# relay_board.net
KiCad netlist of a schematic drawn in EAGLE
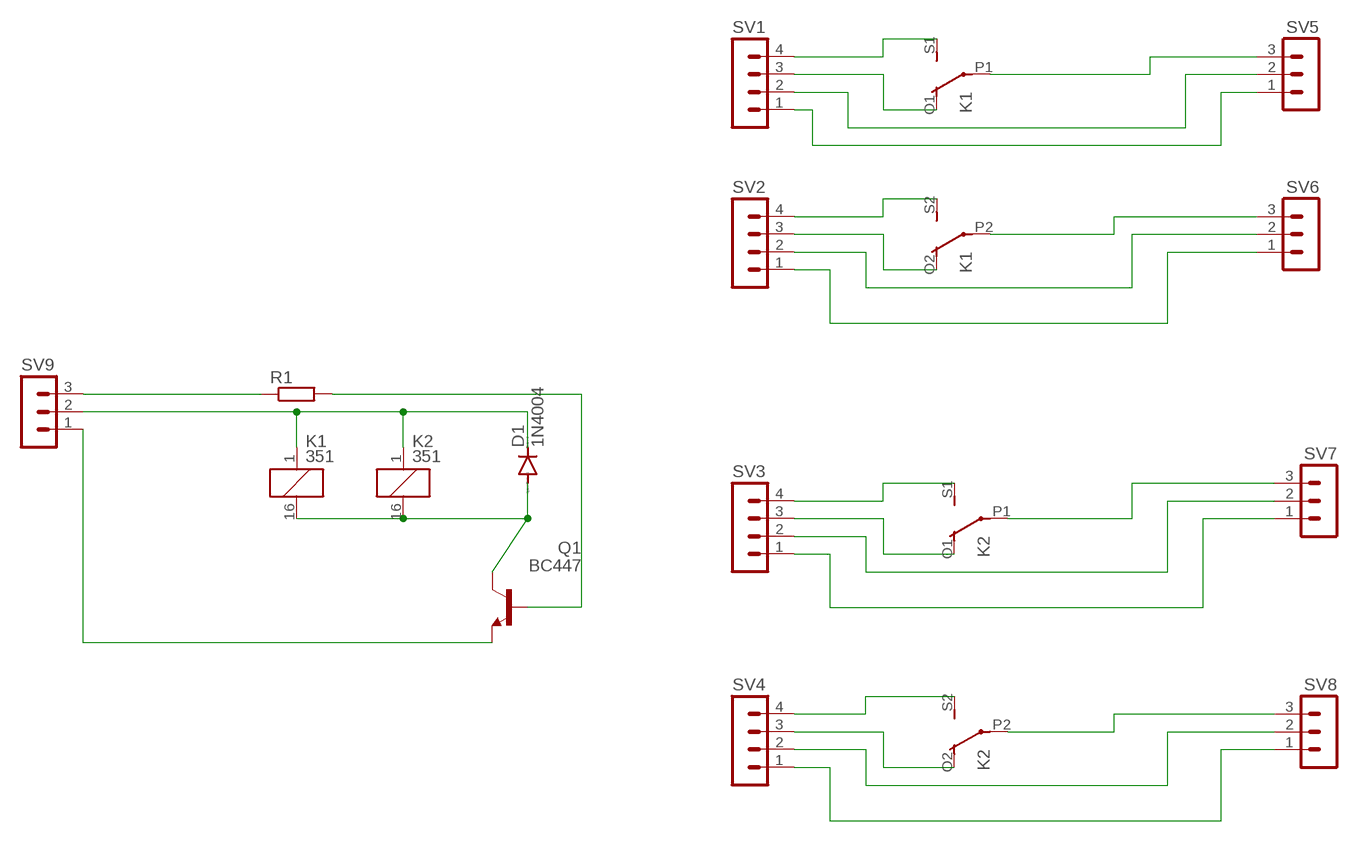
[diagram p0: schematic, sheet 1]

(export (version "E")
  (design (tool "Eeschema 10.0.6"))
  (components
    (comp (ref "D1")
      (value "1N4004")
      (footprint "eagle-import:DO41-10")
      (libsource (lib "eagle-import") (part "1N4004"))
    )
    (comp (ref "K1")
      (value "351")
      (footprint "eagle-import:351")
      (libsource (lib "eagle-import") (part "351"))
    )
    (comp (ref "K2")
      (value "351")
      (footprint "eagle-import:351")
      (libsource (lib "eagle-import") (part "351"))
    )
    (comp (ref "Q1")
      (value "BC447")
      (footprint "eagle-import:TO92-EBC")
      (libsource (lib "eagle-import") (part "BC447"))
    )
    (comp (ref "R1")
      (value "R-EU_0207/15")
      (footprint "eagle-import:0207_15")
      (libsource (lib "eagle-import") (part "R-EU_0207/15"))
    )
    (comp (ref "SV1")
      (value "MA04-1")
      (footprint "eagle-import:MA04-1")
      (libsource (lib "eagle-import") (part "MA04-1"))
    )
    (comp (ref "SV2")
      (value "MA04-1")
      (footprint "eagle-import:MA04-1")
      (libsource (lib "eagle-import") (part "MA04-1"))
    )
    (comp (ref "SV3")
      (value "MA04-1")
      (footprint "eagle-import:MA04-1")
      (libsource (lib "eagle-import") (part "MA04-1"))
    )
    (comp (ref "SV4")
      (value "MA04-1")
      (footprint "eagle-import:MA04-1")
      (libsource (lib "eagle-import") (part "MA04-1"))
    )
    (comp (ref "SV5")
      (value "MA03-1")
      (footprint "eagle-import:MA03-1")
      (libsource (lib "eagle-import") (part "MA03-1"))
    )
    (comp (ref "SV6")
      (value "MA03-1")
      (footprint "eagle-import:MA03-1")
      (libsource (lib "eagle-import") (part "MA03-1"))
    )
    (comp (ref "SV7")
      (value "MA03-1")
      (footprint "eagle-import:MA03-1")
      (libsource (lib "eagle-import") (part "MA03-1"))
    )
    (comp (ref "SV8")
      (value "MA03-1")
      (footprint "eagle-import:MA03-1")
      (libsource (lib "eagle-import") (part "MA03-1"))
    )
    (comp (ref "SV9")
      (value "MA03-1")
      (footprint "eagle-import:MA03-1")
      (libsource (lib "eagle-import") (part "MA03-1"))
    )
  )
  (nets
    (net (code "1") (name "Net-(D1-PadC)") (class "Default")
      (node (ref "D1") (pin "C") (pinfunction "C_C") (pintype "passive"))
      (node (ref "K1") (pin "1") (pinfunction "1_1") (pintype "passive"))
      (node (ref "K2") (pin "1") (pinfunction "1_1") (pintype "passive"))
      (node (ref "SV9") (pin "2") (pinfunction "2_2") (pintype "passive"))
    )
    (net (code "2") (name "Net-(K1A-2)") (class "Default")
      (node (ref "D1") (pin "A") (pinfunction "A_A") (pintype "passive"))
      (node (ref "K1") (pin "16") (pinfunction "2_16") (pintype "passive"))
      (node (ref "K2") (pin "16") (pinfunction "2_16") (pintype "passive"))
      (node (ref "Q1") (pin "C") (pinfunction "C_C") (pintype "passive"))
    )
    (net (code "3") (name "Net-(K1B-O)") (class "Default")
      (node (ref "K1") (pin "O1") (pinfunction "O_O1") (pintype "passive"))
      (node (ref "SV1") (pin "3") (pinfunction "3_3") (pintype "passive"))
    )
    (net (code "4") (name "Net-(K1B-P)") (class "Default")
      (node (ref "K1") (pin "P1") (pinfunction "P_P1") (pintype "passive"))
      (node (ref "SV5") (pin "3") (pinfunction "3_3") (pintype "passive"))
    )
    (net (code "5") (name "Net-(K1B-S)") (class "Default")
      (node (ref "K1") (pin "S1") (pinfunction "S_S1") (pintype "passive"))
      (node (ref "SV1") (pin "4") (pinfunction "4_4") (pintype "passive"))
    )
    (net (code "6") (name "Net-(K1C-O)") (class "Default")
      (node (ref "K1") (pin "O2") (pinfunction "O_O2") (pintype "passive"))
      (node (ref "SV2") (pin "3") (pinfunction "3_3") (pintype "passive"))
    )
    (net (code "7") (name "Net-(K1C-P)") (class "Default")
      (node (ref "K1") (pin "P2") (pinfunction "P_P2") (pintype "passive"))
      (node (ref "SV6") (pin "3") (pinfunction "3_3") (pintype "passive"))
    )
    (net (code "8") (name "Net-(K1C-S)") (class "Default")
      (node (ref "K1") (pin "S2") (pinfunction "S_S2") (pintype "passive"))
      (node (ref "SV2") (pin "4") (pinfunction "4_4") (pintype "passive"))
    )
    (net (code "9") (name "Net-(K2B-O)") (class "Default")
      (node (ref "K2") (pin "O1") (pinfunction "O_O1") (pintype "passive"))
      (node (ref "SV3") (pin "3") (pinfunction "3_3") (pintype "passive"))
    )
    (net (code "10") (name "Net-(K2B-P)") (class "Default")
      (node (ref "K2") (pin "P1") (pinfunction "P_P1") (pintype "passive"))
      (node (ref "SV7") (pin "3") (pinfunction "3_3") (pintype "passive"))
    )
    (net (code "11") (name "Net-(K2B-S)") (class "Default")
      (node (ref "K2") (pin "S1") (pinfunction "S_S1") (pintype "passive"))
      (node (ref "SV3") (pin "4") (pinfunction "4_4") (pintype "passive"))
    )
    (net (code "12") (name "Net-(K2C-O)") (class "Default")
      (node (ref "K2") (pin "O2") (pinfunction "O_O2") (pintype "passive"))
      (node (ref "SV4") (pin "3") (pinfunction "3_3") (pintype "passive"))
    )
    (net (code "13") (name "Net-(K2C-P)") (class "Default")
      (node (ref "K2") (pin "P2") (pinfunction "P_P2") (pintype "passive"))
      (node (ref "SV8") (pin "3") (pinfunction "3_3") (pintype "passive"))
    )
    (net (code "14") (name "Net-(K2C-S)") (class "Default")
      (node (ref "K2") (pin "S2") (pinfunction "S_S2") (pintype "passive"))
      (node (ref "SV4") (pin "4") (pinfunction "4_4") (pintype "passive"))
    )
    (net (code "15") (name "Net-(Q1-PadB)") (class "Default")
      (node (ref "Q1") (pin "B") (pinfunction "B_B") (pintype "passive"))
      (node (ref "R1") (pin "2") (pinfunction "2_2") (pintype "passive"))
    )
    (net (code "16") (name "Net-(Q1-PadE)") (class "Default")
      (node (ref "Q1") (pin "E") (pinfunction "E_E") (pintype "passive"))
      (node (ref "SV9") (pin "1") (pinfunction "1_1") (pintype "passive"))
    )
    (net (code "17") (name "Net-(R1-Pad1)") (class "Default")
      (node (ref "R1") (pin "1") (pinfunction "1_1") (pintype "passive"))
      (node (ref "SV9") (pin "3") (pinfunction "3_3") (pintype "passive"))
    )
    (net (code "18") (name "Net-(SV1-Pad1)") (class "Default")
      (node (ref "SV1") (pin "1") (pinfunction "1_1") (pintype "passive"))
      (node (ref "SV5") (pin "1") (pinfunction "1_1") (pintype "passive"))
    )
    (net (code "19") (name "Net-(SV1-Pad2)") (class "Default")
      (node (ref "SV1") (pin "2") (pinfunction "2_2") (pintype "passive"))
      (node (ref "SV5") (pin "2") (pinfunction "2_2") (pintype "passive"))
    )
    (net (code "20") (name "Net-(SV2-Pad1)") (class "Default")
      (node (ref "SV2") (pin "1") (pinfunction "1_1") (pintype "passive"))
      (node (ref "SV6") (pin "1") (pinfunction "1_1") (pintype "passive"))
    )
    (net (code "21") (name "Net-(SV2-Pad2)") (class "Default")
      (node (ref "SV2") (pin "2") (pinfunction "2_2") (pintype "passive"))
      (node (ref "SV6") (pin "2") (pinfunction "2_2") (pintype "passive"))
    )
    (net (code "22") (name "Net-(SV3-Pad1)") (class "Default")
      (node (ref "SV3") (pin "1") (pinfunction "1_1") (pintype "passive"))
      (node (ref "SV7") (pin "1") (pinfunction "1_1") (pintype "passive"))
    )
    (net (code "23") (name "Net-(SV3-Pad2)") (class "Default")
      (node (ref "SV3") (pin "2") (pinfunction "2_2") (pintype "passive"))
      (node (ref "SV7") (pin "2") (pinfunction "2_2") (pintype "passive"))
    )
    (net (code "24") (name "Net-(SV4-Pad1)") (class "Default")
      (node (ref "SV4") (pin "1") (pinfunction "1_1") (pintype "passive"))
      (node (ref "SV8") (pin "1") (pinfunction "1_1") (pintype "passive"))
    )
    (net (code "25") (name "Net-(SV4-Pad2)") (class "Default")
      (node (ref "SV4") (pin "2") (pinfunction "2_2") (pintype "passive"))
      (node (ref "SV8") (pin "2") (pinfunction "2_2") (pintype "passive"))
    )
  )
)
